# DualMonoPSU2.net
KiCad netlist of a schematic drawn in EAGLE
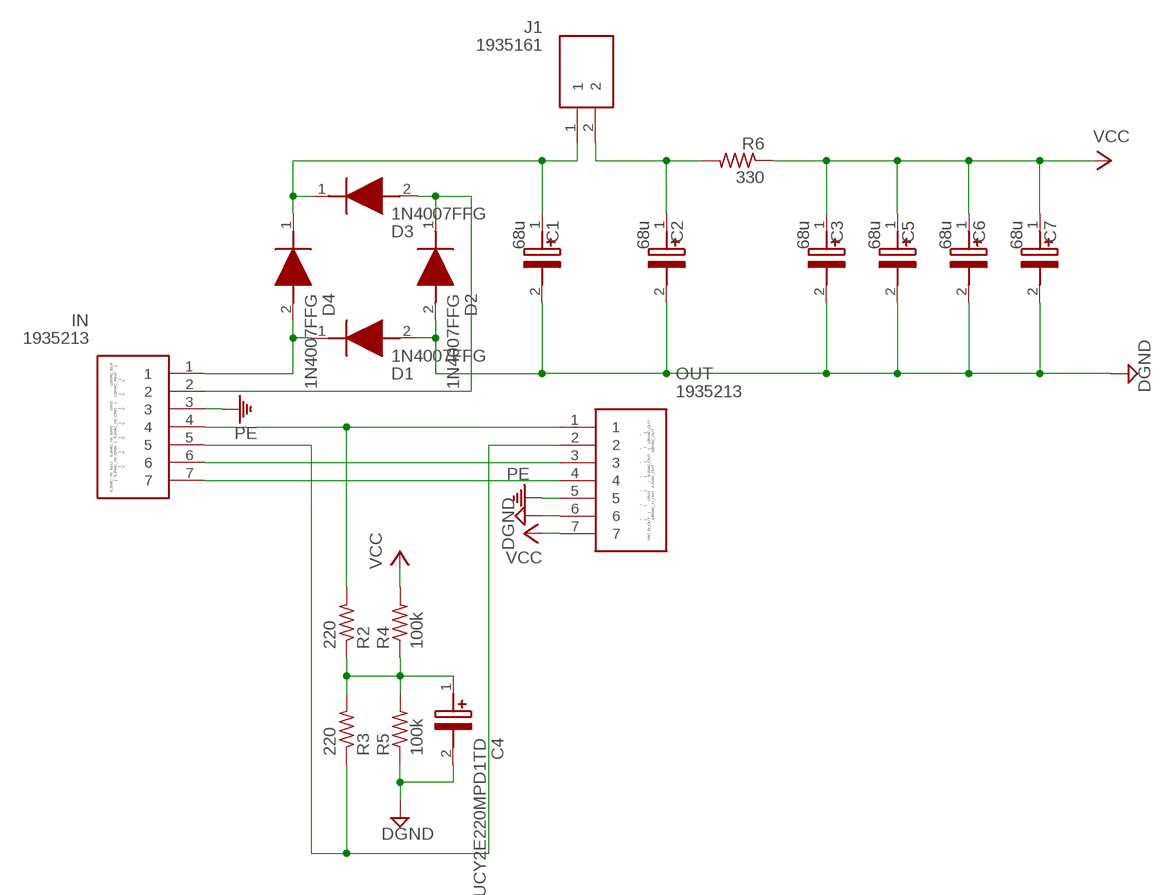
[diagram p0: schematic, sheet 1]

(export (version "E")
  (design (tool "Eeschema 10.0.6"))
  (components
    (comp (ref "C1")
      (value "68u")
      (footprint "eagle-import:CAPPRD750W80D1475H4700")
      (fields (field (name "MANUFACTURER_PART_NUMBER") "500HXW68MEFR14.5X45"))
      (libsource (lib "eagle-import") (part "500HXW68MEFR14.5X45"))
    )
    (comp (ref "C2")
      (value "68u")
      (footprint "eagle-import:CAPPRD750W80D1475H4700")
      (fields (field (name "MANUFACTURER_PART_NUMBER") "500HXW68MEFR14.5X45"))
      (libsource (lib "eagle-import") (part "500HXW68MEFR14.5X45"))
    )
    (comp (ref "C3")
      (value "68u")
      (footprint "eagle-import:CAPPRD750W80D1475H4700")
      (fields (field (name "MANUFACTURER_PART_NUMBER") "500HXW68MEFR14.5X45"))
      (libsource (lib "eagle-import") (part "500HXW68MEFR14.5X45"))
    )
    (comp (ref "C4")
      (value "UCY2E220MPD1TD")
      (footprint "eagle-import:CAPPRD500W60D1025H1750")
      (fields (field (name "MOUSER_PART_NUMBER") "647-UCY2E220MPD1TD"))
      (libsource (lib "eagle-import") (part "UCY2E220MPD1TD"))
    )
    (comp (ref "C5")
      (value "68u")
      (footprint "eagle-import:CAPPRD750W80D1475H4700")
      (fields (field (name "MANUFACTURER_PART_NUMBER") "500HXW68MEFR14.5X45"))
      (libsource (lib "eagle-import") (part "500HXW68MEFR14.5X45"))
    )
    (comp (ref "C6")
      (value "68u")
      (footprint "eagle-import:CAPPRD750W80D1475H4700")
      (fields (field (name "MANUFACTURER_PART_NUMBER") "500HXW68MEFR14.5X45"))
      (libsource (lib "eagle-import") (part "500HXW68MEFR14.5X45"))
    )
    (comp (ref "C7")
      (value "68u")
      (footprint "eagle-import:CAPPRD750W80D1475H4700")
      (fields (field (name "MANUFACTURER_PART_NUMBER") "500HXW68MEFR14.5X45"))
      (libsource (lib "eagle-import") (part "500HXW68MEFR14.5X45"))
    )
    (comp (ref "D1")
      (value "1N4007FFG")
      (footprint "eagle-import:DIOAD1405W86L465D235")
      (fields (field (name "MOUSER_PART_NUMBER") "863-1N4007FFG"))
      (libsource (lib "eagle-import") (part "1N4007FFG"))
    )
    (comp (ref "D2")
      (value "1N4007FFG")
      (footprint "eagle-import:DIOAD1405W86L465D235")
      (fields (field (name "MOUSER_PART_NUMBER") "863-1N4007FFG"))
      (libsource (lib "eagle-import") (part "1N4007FFG"))
    )
    (comp (ref "D3")
      (value "1N4007FFG")
      (footprint "eagle-import:DIOAD1405W86L465D235")
      (fields (field (name "MOUSER_PART_NUMBER") "863-1N4007FFG"))
      (libsource (lib "eagle-import") (part "1N4007FFG"))
    )
    (comp (ref "D4")
      (value "1N4007FFG")
      (footprint "eagle-import:DIOAD1405W86L465D235")
      (fields (field (name "MOUSER_PART_NUMBER") "863-1N4007FFG"))
      (libsource (lib "eagle-import") (part "1N4007FFG"))
    )
    (comp (ref "IN")
      (value "1935213")
      (footprint "eagle-import:1935213")
      (fields (field (name "MOUSER_PART_NUMBER") "651-1935213"))
      (libsource (lib "eagle-import") (part "1935213"))
    )
    (comp (ref "J1")
      (value "1935161")
      (footprint "eagle-import:1935161")
      (fields (field (name "MOUSER_PART_NUMBER") "651-1935161"))
      (libsource (lib "eagle-import") (part "1935161"))
    )
    (comp (ref "OUT")
      (value "1935213")
      (footprint "eagle-import:1935213")
      (fields (field (name "MOUSER_PART_NUMBER") "651-1935213"))
      (libsource (lib "eagle-import") (part "1935213"))
    )
    (comp (ref "R2")
      (value "220")
      (footprint "eagle-import:0411_15")
      (libsource (lib "eagle-import") (part "R-US_0411/15"))
    )
    (comp (ref "R3")
      (value "220")
      (footprint "eagle-import:0411_15")
      (libsource (lib "eagle-import") (part "R-US_0411/15"))
    )
    (comp (ref "R4")
      (value "100k")
      (footprint "eagle-import:0411_15")
      (libsource (lib "eagle-import") (part "R-US_0411/15"))
    )
    (comp (ref "R5")
      (value "100k")
      (footprint "eagle-import:0411_15")
      (libsource (lib "eagle-import") (part "R-US_0411/15"))
    )
    (comp (ref "R6")
      (value "330")
      (footprint "eagle-import:0411_15")
      (libsource (lib "eagle-import") (part "R-US_0411/15"))
    )
  )
  (nets
    (net (code "1") (name "DGND") (class "Default")
      (node (ref "C1") (pin "2") (pinfunction "-_2") (pintype "bidirectional"))
      (node (ref "C2") (pin "2") (pinfunction "-_2") (pintype "bidirectional"))
      (node (ref "C3") (pin "2") (pinfunction "-_2") (pintype "bidirectional"))
      (node (ref "C4") (pin "2") (pinfunction "-_2") (pintype "bidirectional"))
      (node (ref "C5") (pin "2") (pinfunction "-_2") (pintype "bidirectional"))
      (node (ref "C6") (pin "2") (pinfunction "-_2") (pintype "bidirectional"))
      (node (ref "C7") (pin "2") (pinfunction "-_2") (pintype "bidirectional"))
      (node (ref "D1") (pin "2") (pinfunction "A_2") (pintype "bidirectional"))
      (node (ref "D2") (pin "2") (pinfunction "A_2") (pintype "bidirectional"))
      (node (ref "OUT") (pin "6") (pinfunction "6_6") (pintype "bidirectional"))
      (node (ref "R5") (pin "1") (pinfunction "1_1") (pintype "passive"))
    )
    (net (code "2") (name "Net-(C1-+)") (class "Default")
      (node (ref "C1") (pin "1") (pinfunction "+_1") (pintype "bidirectional"))
      (node (ref "D3") (pin "1") (pinfunction "K_1") (pintype "bidirectional"))
      (node (ref "D4") (pin "1") (pinfunction "K_1") (pintype "bidirectional"))
      (node (ref "J1") (pin "1") (pinfunction "1_1") (pintype "bidirectional"))
    )
    (net (code "3") (name "Net-(C2-+)") (class "Default")
      (node (ref "C2") (pin "1") (pinfunction "+_1") (pintype "bidirectional"))
      (node (ref "J1") (pin "2") (pinfunction "2_2") (pintype "bidirectional"))
      (node (ref "R6") (pin "2") (pinfunction "2_2") (pintype "passive"))
    )
    (net (code "4") (name "Net-(C4-+)") (class "Default")
      (node (ref "C4") (pin "1") (pinfunction "+_1") (pintype "bidirectional"))
      (node (ref "R2") (pin "1") (pinfunction "1_1") (pintype "passive"))
      (node (ref "R3") (pin "2") (pinfunction "2_2") (pintype "passive"))
      (node (ref "R4") (pin "1") (pinfunction "1_1") (pintype "passive"))
      (node (ref "R5") (pin "2") (pinfunction "2_2") (pintype "passive"))
    )
    (net (code "5") (name "Net-(D1-K)") (class "Default")
      (node (ref "D1") (pin "1") (pinfunction "K_1") (pintype "bidirectional"))
      (node (ref "D4") (pin "2") (pinfunction "A_2") (pintype "bidirectional"))
      (node (ref "IN") (pin "1") (pinfunction "1_1") (pintype "bidirectional"))
    )
    (net (code "6") (name "Net-(D2-K)") (class "Default")
      (node (ref "D2") (pin "1") (pinfunction "K_1") (pintype "bidirectional"))
      (node (ref "D3") (pin "2") (pinfunction "A_2") (pintype "bidirectional"))
      (node (ref "IN") (pin "2") (pinfunction "2_2") (pintype "bidirectional"))
    )
    (net (code "7") (name "Net-(IN-Pad4)") (class "Default")
      (node (ref "IN") (pin "4") (pinfunction "4_4") (pintype "bidirectional"))
      (node (ref "OUT") (pin "1") (pinfunction "1_1") (pintype "bidirectional"))
      (node (ref "R2") (pin "2") (pinfunction "2_2") (pintype "passive"))
    )
    (net (code "8") (name "Net-(IN-Pad5)") (class "Default")
      (node (ref "IN") (pin "5") (pinfunction "5_5") (pintype "bidirectional"))
      (node (ref "OUT") (pin "2") (pinfunction "2_2") (pintype "bidirectional"))
      (node (ref "R3") (pin "1") (pinfunction "1_1") (pintype "passive"))
    )
    (net (code "9") (name "Net-(IN-Pad6)") (class "Default")
      (node (ref "IN") (pin "6") (pinfunction "6_6") (pintype "bidirectional"))
      (node (ref "OUT") (pin "3") (pinfunction "3_3") (pintype "bidirectional"))
    )
    (net (code "10") (name "Net-(IN-Pad7)") (class "Default")
      (node (ref "IN") (pin "7") (pinfunction "7_7") (pintype "bidirectional"))
      (node (ref "OUT") (pin "4") (pinfunction "4_4") (pintype "bidirectional"))
    )
    (net (code "11") (name "PE") (class "Default")
      (node (ref "IN") (pin "3") (pinfunction "3_3") (pintype "bidirectional"))
      (node (ref "OUT") (pin "5") (pinfunction "5_5") (pintype "bidirectional"))
    )
    (net (code "12") (name "VCC") (class "Default")
      (node (ref "C3") (pin "1") (pinfunction "+_1") (pintype "bidirectional"))
      (node (ref "C5") (pin "1") (pinfunction "+_1") (pintype "bidirectional"))
      (node (ref "C6") (pin "1") (pinfunction "+_1") (pintype "bidirectional"))
      (node (ref "C7") (pin "1") (pinfunction "+_1") (pintype "bidirectional"))
      (node (ref "OUT") (pin "7") (pinfunction "7_7") (pintype "bidirectional"))
      (node (ref "R4") (pin "2") (pinfunction "2_2") (pintype "passive"))
      (node (ref "R6") (pin "1") (pinfunction "1_1") (pintype "passive"))
    )
  )
)
